# amp_comp.net
KiCad netlist of a schematic drawn in Altium Designer
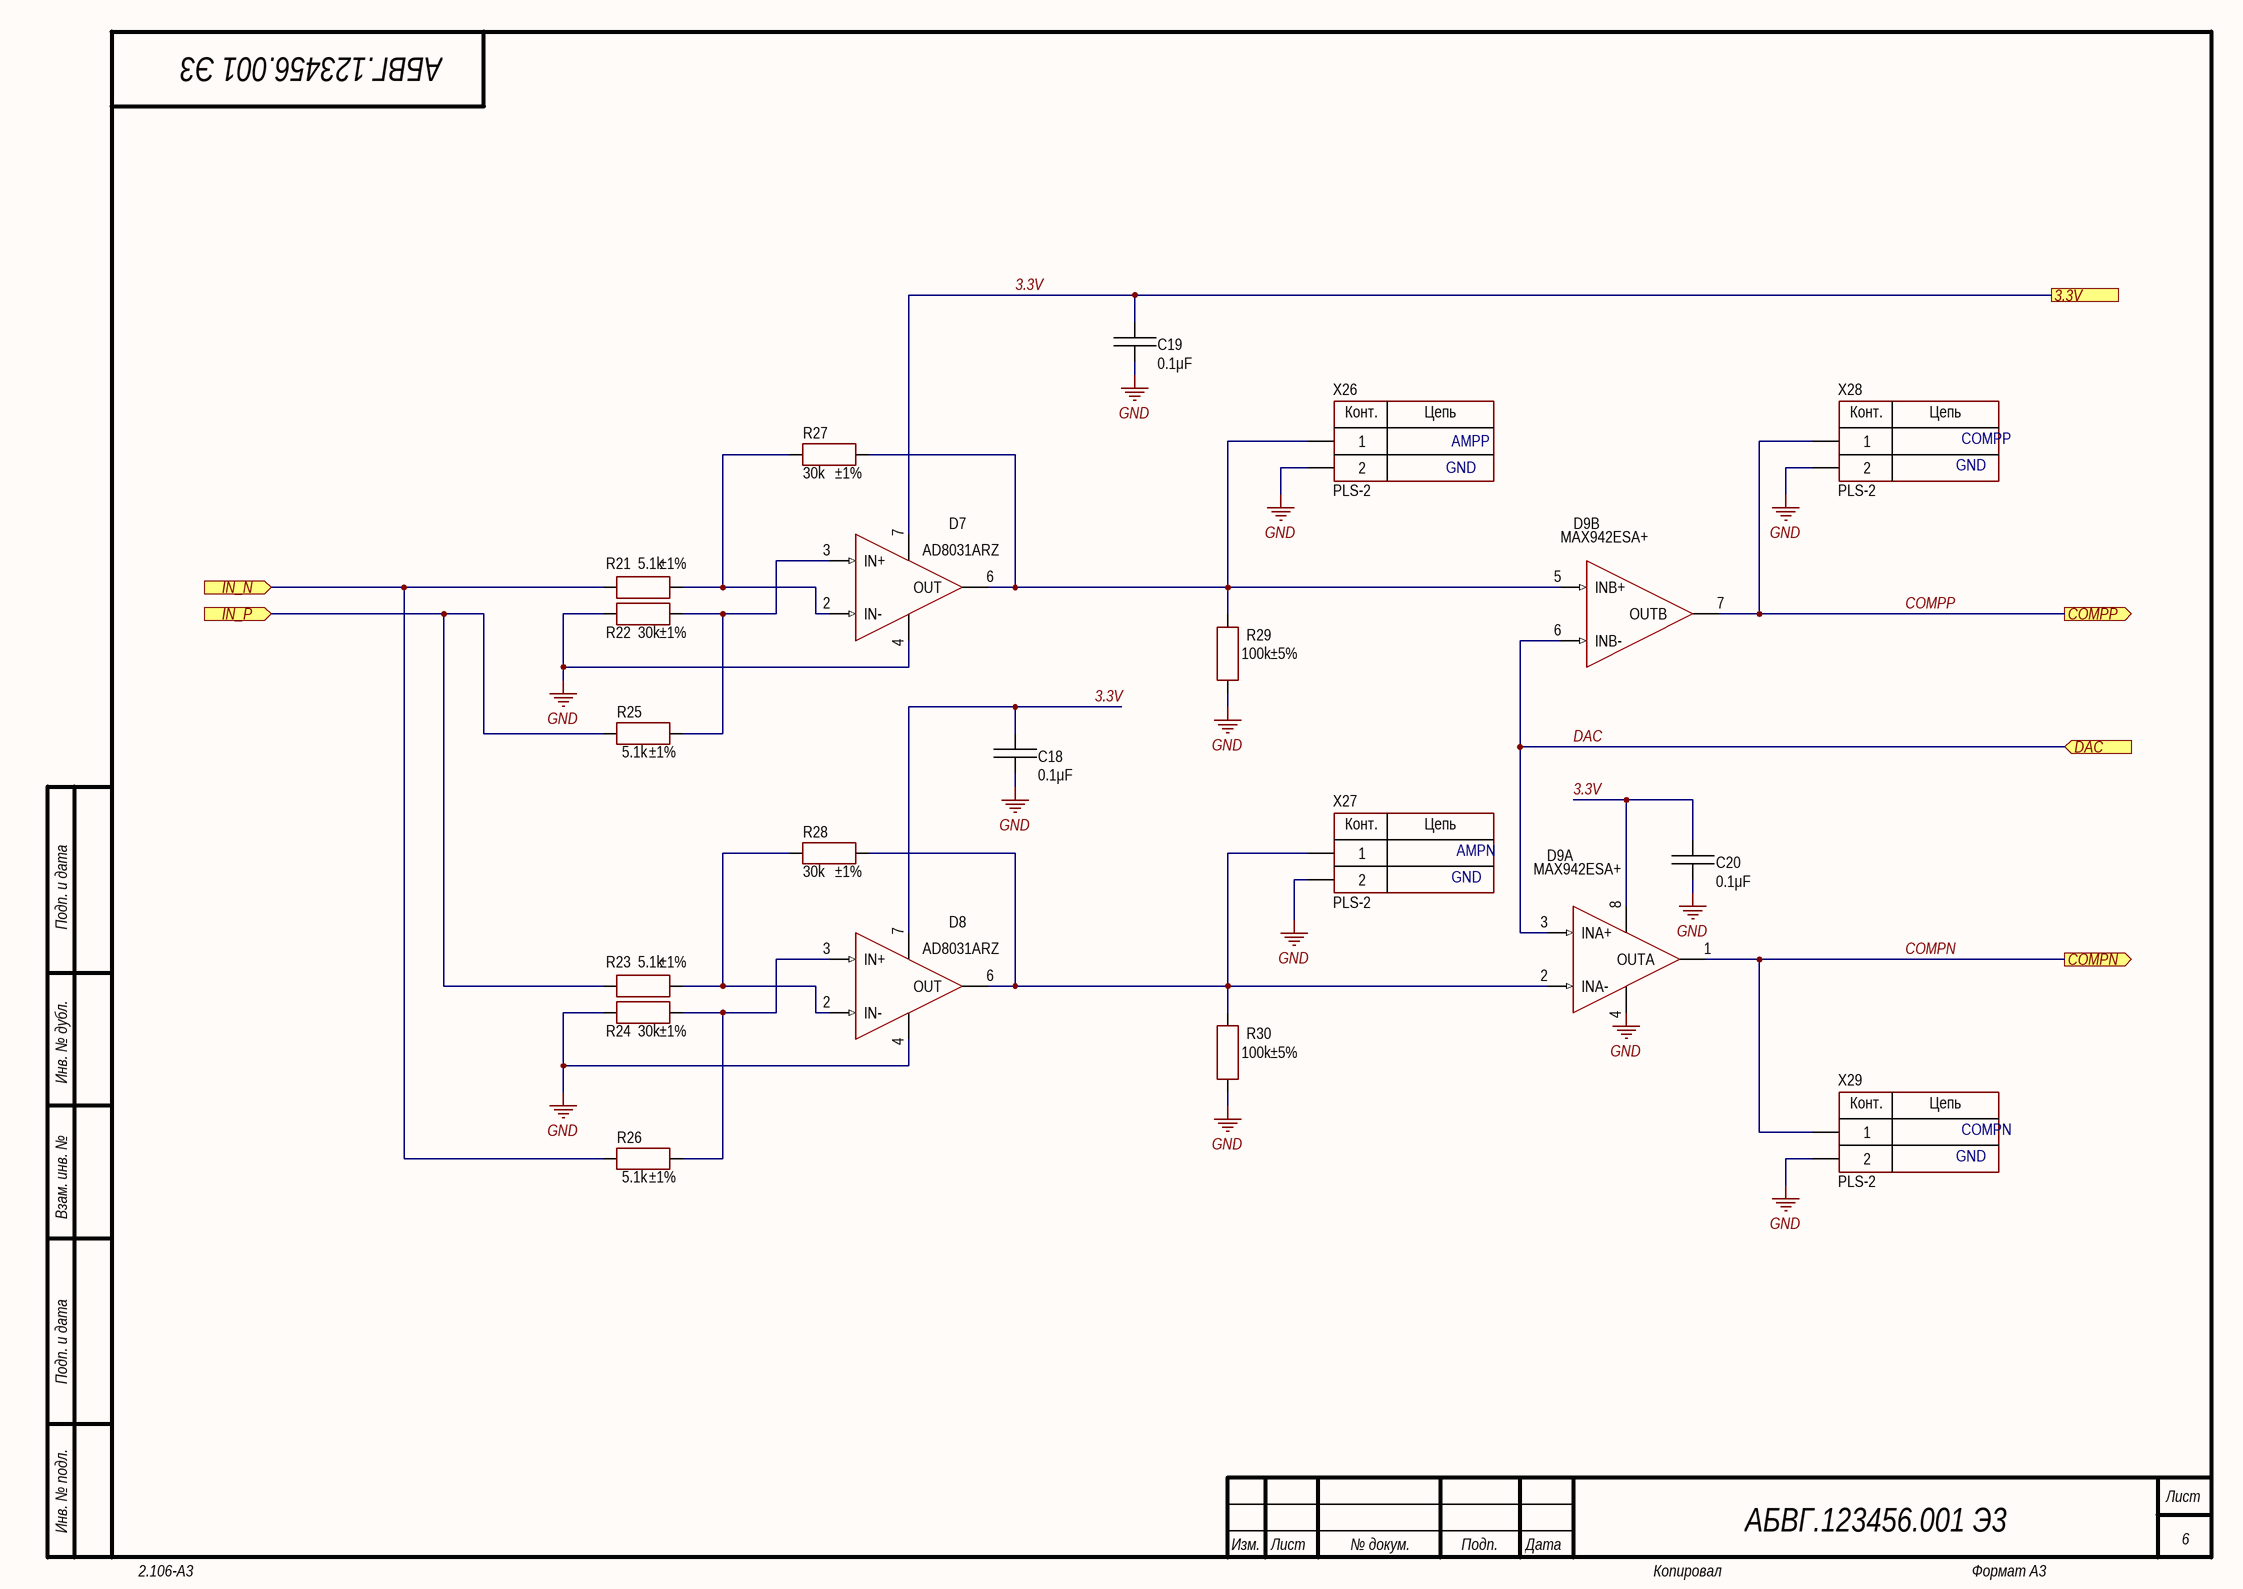
[diagram p0: amp_comp.SchDoc]

(export (version "E")
  (design (tool "Eeschema 10.0.6"))
  (components
    (comp (ref "C18")
      (value "0.1μF")
      (footprint "CAP: 1206")
      (fields
        (field (name "MANUFACTURER") "Murata Electronics")
        (field (name "PARTNUMBER") "GRM319R71H104K")
        (field (name "VALUEMANUFACTURERPARTNUMBER") "Ceramic capacitor, 0.1μF, X7R, ±10%, 50V, 1206, -55...+125°C")
      )
      (libsource (lib "capacitor") (part "Ceramic_1206"))
    )
    (comp (ref "C19")
      (value "0.1μF")
      (footprint "CAP: 1206")
      (fields
        (field (name "MANUFACTURER") "Murata Electronics")
        (field (name "PARTNUMBER") "GRM319R71H104K")
        (field (name "VALUEMANUFACTURERPARTNUMBER") "Ceramic capacitor, 0.1μF, X7R, ±10%, 50V, 1206, -55...+125°C")
      )
      (libsource (lib "capacitor") (part "Ceramic_1206"))
    )
    (comp (ref "C20")
      (value "0.1μF")
      (footprint "CAP: 1206")
      (fields
        (field (name "MANUFACTURER") "Murata Electronics")
        (field (name "PARTNUMBER") "GRM319R71H104K")
        (field (name "VALUEMANUFACTURERPARTNUMBER") "Ceramic capacitor, 0.1μF, X7R, ±10%, 50V, 1206, -55...+125°C")
      )
      (libsource (lib "capacitor") (part "Ceramic_1206"))
    )
    (comp (ref "D7")
      (value "~")
      (footprint "8-SOIC")
      (description "OP amplifier")
      (fields
        (field (name "MANUFACTURER") "Analog Devices Inc.")
        (field (name "VALUEMANUFACTURERPARTNUMBER") "IC op amplifier, Rail-to-Rail, 80MHz, 2.7V ~ 12V, ±1.35V ~ 6V, -40°C ~ 85°C, 8-SOIC")
        (field (name "PARTNUMBER") "AD8031ARZ")
      )
      (libsource (lib "ic-amplifier") (part "AD8031ARZ"))
    )
    (comp (ref "D8")
      (value "~")
      (footprint "8-SOIC")
      (description "OP amplifier")
      (fields
        (field (name "MANUFACTURER") "Analog Devices Inc.")
        (field (name "VALUEMANUFACTURERPARTNUMBER") "IC op amplifier, Rail-to-Rail, 80MHz, 2.7V ~ 12V, ±1.35V ~ 6V, -40°C ~ 85°C, 8-SOIC")
        (field (name "PARTNUMBER") "AD8031ARZ")
      )
      (libsource (lib "ic-amplifier") (part "AD8031ARZ"))
    )
    (comp (ref "D9")
      (value "~")
      (footprint "8-SOIC")
      (description "Comparator")
      (fields
        (field (name "MANUFACTURER") "Maxim Integrated Products")
        (field (name "VALUEMANUFACTURERPARTNUMBER") "IC comparator, Rail-to-Rail, 2.7…6V, -40…85°C, DIP-8(P)/SOIC-8(S)")
        (field (name "PARTNUMBER") "MAX942ESA+")
      )
      (libsource (lib "ic-comparator") (part "MAX942ExA+"))
    )
    (comp (ref "R21")
      (value "5.1k")
      (footprint "RES: 1206")
      (fields
        (field (name "MANUFACTURER") "Yageo")
        (field (name "PARTNUMBER") "RC1206JR-07100RL")
        (field (name "VALUEMANUFACTURERPARTNUMBER") "Resistor film, 5.1k, ±1%, 1206, 0.25W, -55...+125°C")
        (field (name "TOLERANCE") "±1%")
      )
      (libsource (lib "resistor") (part "Resistor_1206"))
    )
    (comp (ref "R22")
      (value "30k")
      (footprint "RES: 1206")
      (fields
        (field (name "MANUFACTURER") "Yageo")
        (field (name "PARTNUMBER") "RC1206JR-07100RL")
        (field (name "VALUEMANUFACTURERPARTNUMBER") "Resistor film, 30k, ±1%, 1206, 0.25W, -55...+125°C")
        (field (name "TOLERANCE") "±1%")
      )
      (libsource (lib "resistor") (part "Resistor_1206"))
    )
    (comp (ref "R23")
      (value "5.1k")
      (footprint "RES: 1206")
      (fields
        (field (name "MANUFACTURER") "Yageo")
        (field (name "PARTNUMBER") "RC1206JR-07100RL")
        (field (name "VALUEMANUFACTURERPARTNUMBER") "Resistor film, 5.1k, ±1%, 1206, 0.25W, -55...+125°C")
        (field (name "TOLERANCE") "±1%")
      )
      (libsource (lib "resistor") (part "Resistor_1206"))
    )
    (comp (ref "R24")
      (value "30k")
      (footprint "RES: 1206")
      (fields
        (field (name "MANUFACTURER") "Yageo")
        (field (name "PARTNUMBER") "RC1206JR-07100RL")
        (field (name "VALUEMANUFACTURERPARTNUMBER") "Resistor film, 30k, ±1%, 1206, 0.25W, -55...+125°C")
        (field (name "TOLERANCE") "±1%")
      )
      (libsource (lib "resistor") (part "Resistor_1206"))
    )
    (comp (ref "R25")
      (value "5.1k")
      (footprint "RES: 1206")
      (fields
        (field (name "MANUFACTURER") "Yageo")
        (field (name "PARTNUMBER") "RC1206JR-07100RL")
        (field (name "VALUEMANUFACTURERPARTNUMBER") "Resistor film, 5.1k, ±1%, 1206, 0.25W, -55...+125°C")
        (field (name "TOLERANCE") "±1%")
      )
      (libsource (lib "resistor") (part "Resistor_1206"))
    )
    (comp (ref "R26")
      (value "5.1k")
      (footprint "RES: 1206")
      (fields
        (field (name "MANUFACTURER") "Yageo")
        (field (name "PARTNUMBER") "RC1206JR-07100RL")
        (field (name "VALUEMANUFACTURERPARTNUMBER") "Resistor film, 5.1k, ±1%, 1206, 0.25W, -55...+125°C")
        (field (name "TOLERANCE") "±1%")
      )
      (libsource (lib "resistor") (part "Resistor_1206"))
    )
    (comp (ref "R27")
      (value "30k")
      (footprint "RES: 1206")
      (fields
        (field (name "MANUFACTURER") "Yageo")
        (field (name "PARTNUMBER") "RC1206JR-07100RL")
        (field (name "VALUEMANUFACTURERPARTNUMBER") "Resistor film, 30k, ±1%, 1206, 0.25W, -55...+125°C")
        (field (name "TOLERANCE") "±1%")
      )
      (libsource (lib "resistor") (part "Resistor_1206"))
    )
    (comp (ref "R28")
      (value "30k")
      (footprint "RES: 1206")
      (fields
        (field (name "MANUFACTURER") "Yageo")
        (field (name "PARTNUMBER") "RC1206JR-07100RL")
        (field (name "VALUEMANUFACTURERPARTNUMBER") "Resistor film, 30k, ±1%, 1206, 0.25W, -55...+125°C")
        (field (name "TOLERANCE") "±1%")
      )
      (libsource (lib "resistor") (part "Resistor_1206"))
    )
    (comp (ref "R29")
      (value "100k")
      (footprint "RES: 1206")
      (fields
        (field (name "MANUFACTURER") "Yageo")
        (field (name "PARTNUMBER") "RC1206JR-07100RL")
        (field (name "VALUEMANUFACTURERPARTNUMBER") "Resistor film, 100k, ±5%, 1206, 0.25W, -55...+125°C")
        (field (name "TOLERANCE") "±5%")
      )
      (libsource (lib "") (part "Resistor_1206_1"))
    )
    (comp (ref "R30")
      (value "100k")
      (footprint "RES: 1206")
      (fields
        (field (name "MANUFACTURER") "Yageo")
        (field (name "PARTNUMBER") "RC1206JR-07100RL")
        (field (name "VALUEMANUFACTURERPARTNUMBER") "Resistor film, 100k, ±5%, 1206, 0.25W, -55...+125°C")
        (field (name "TOLERANCE") "±5%")
      )
      (libsource (lib "") (part "Resistor_1206_1"))
    )
    (comp (ref "X26")
      (value "~")
      (footprint "CON: PLS-2")
      (fields
        (field (name "MANUFACTURER") "Connfly")
        (field (name "VALUEMANUFACTURERPARTNUMBER") "Connector, 2pin, 2.54mm, 500VAC, 3A")
        (field (name "PARTNUMBER") "PLS-2")
        (field (name "COMMENTTEXT") "PLS-2")
      )
      (libsource (lib "connector") (part "PLS-2"))
    )
    (comp (ref "X27")
      (value "~")
      (footprint "CON: PLS-2")
      (fields
        (field (name "MANUFACTURER") "Connfly")
        (field (name "VALUEMANUFACTURERPARTNUMBER") "Connector, 2pin, 2.54mm, 500VAC, 3A")
        (field (name "PARTNUMBER") "PLS-2")
        (field (name "COMMENTTEXT") "PLS-2")
      )
      (libsource (lib "connector") (part "PLS-2"))
    )
    (comp (ref "X28")
      (value "~")
      (footprint "CON: PLS-2")
      (fields
        (field (name "MANUFACTURER") "Connfly")
        (field (name "VALUEMANUFACTURERPARTNUMBER") "Connector, 2pin, 2.54mm, 500VAC, 3A")
        (field (name "PARTNUMBER") "PLS-2")
        (field (name "COMMENTTEXT") "PLS-2")
      )
      (libsource (lib "connector") (part "PLS-2"))
    )
    (comp (ref "X29")
      (value "~")
      (footprint "CON: PLS-2")
      (fields
        (field (name "MANUFACTURER") "Connfly")
        (field (name "VALUEMANUFACTURERPARTNUMBER") "Connector, 2pin, 2.54mm, 500VAC, 3A")
        (field (name "PARTNUMBER") "PLS-2")
        (field (name "COMMENTTEXT") "PLS-2")
      )
      (libsource (lib "connector") (part "PLS-2"))
    )
  )
  (nets
    (net (code "1") (name "/3.3V") (class "Default")
      (node (ref "C18") (pin "2") (pinfunction "2_2") (pintype "passive"))
      (node (ref "C19") (pin "2") (pinfunction "2_2") (pintype "passive"))
      (node (ref "C20") (pin "2") (pinfunction "2_2") (pintype "passive"))
      (node (ref "D7") (pin "7") (pinfunction "V+_7") (pintype "power_in"))
      (node (ref "D8") (pin "7") (pinfunction "V+_7") (pintype "power_in"))
      (node (ref "D9") (pin "8") (pinfunction "V+_8") (pintype "power_in"))
    )
    (net (code "2") (name "/COMPN") (class "Default")
      (node (ref "D9") (pin "1") (pinfunction "OUTA_1") (pintype "passive"))
      (node (ref "X29") (pin "1") (pinfunction "1_1") (pintype "passive"))
    )
    (net (code "3") (name "/COMPP") (class "Default")
      (node (ref "D9") (pin "7") (pinfunction "OUTB_7") (pintype "passive"))
      (node (ref "X28") (pin "1") (pinfunction "1_1") (pintype "passive"))
    )
    (net (code "4") (name "/DAC") (class "Default")
      (node (ref "D9") (pin "3") (pinfunction "INA+_3") (pintype "input"))
      (node (ref "D9") (pin "6") (pinfunction "INB-_6") (pintype "input"))
    )
    (net (code "5") (name "/IN_N") (class "Default")
      (node (ref "R21") (pin "2") (pinfunction "2_2") (pintype "passive"))
      (node (ref "R26") (pin "2") (pinfunction "2_2") (pintype "passive"))
    )
    (net (code "6") (name "/IN_P") (class "Default")
      (node (ref "R23") (pin "2") (pinfunction "2_2") (pintype "passive"))
      (node (ref "R25") (pin "2") (pinfunction "2_2") (pintype "passive"))
    )
    (net (code "7") (name "GND") (class "Default")
      (node (ref "C18") (pin "1") (pinfunction "1_1") (pintype "passive"))
      (node (ref "C19") (pin "1") (pinfunction "1_1") (pintype "passive"))
      (node (ref "C20") (pin "1") (pinfunction "1_1") (pintype "passive"))
      (node (ref "D7") (pin "4") (pinfunction "V-_4") (pintype "power_in"))
      (node (ref "D8") (pin "4") (pinfunction "V-_4") (pintype "power_in"))
      (node (ref "D9") (pin "4") (pinfunction "GND_4") (pintype "power_in"))
      (node (ref "R22") (pin "2") (pinfunction "2_2") (pintype "passive"))
      (node (ref "R24") (pin "2") (pinfunction "2_2") (pintype "passive"))
      (node (ref "R29") (pin "1") (pinfunction "1_1") (pintype "passive"))
      (node (ref "R30") (pin "1") (pinfunction "1_1") (pintype "passive"))
      (node (ref "X26") (pin "2") (pinfunction "2_2") (pintype "passive"))
      (node (ref "X27") (pin "2") (pinfunction "2_2") (pintype "passive"))
      (node (ref "X28") (pin "2") (pinfunction "2_2") (pintype "passive"))
      (node (ref "X29") (pin "2") (pinfunction "2_2") (pintype "passive"))
    )
    (net (code "8") (name "Net-(D7-IN+)") (class "Default")
      (node (ref "D7") (pin "3") (pinfunction "IN+_3") (pintype "input"))
      (node (ref "R22") (pin "1") (pinfunction "1_1") (pintype "passive"))
      (node (ref "R25") (pin "1") (pinfunction "1_1") (pintype "passive"))
    )
    (net (code "9") (name "Net-(D7-IN-)") (class "Default")
      (node (ref "D7") (pin "2") (pinfunction "IN-_2") (pintype "input"))
      (node (ref "R21") (pin "1") (pinfunction "1_1") (pintype "passive"))
      (node (ref "R27") (pin "2") (pinfunction "2_2") (pintype "passive"))
    )
    (net (code "10") (name "Net-(D7-OUT)") (class "Default")
      (node (ref "D7") (pin "6") (pinfunction "OUT_6") (pintype "power_in"))
      (node (ref "D9") (pin "5") (pinfunction "INB+_5") (pintype "input"))
      (node (ref "R27") (pin "1") (pinfunction "1_1") (pintype "passive"))
      (node (ref "R29") (pin "2") (pinfunction "2_2") (pintype "passive"))
      (node (ref "X26") (pin "1") (pinfunction "1_1") (pintype "passive"))
    )
    (net (code "11") (name "Net-(D8-IN+)") (class "Default")
      (node (ref "D8") (pin "3") (pinfunction "IN+_3") (pintype "input"))
      (node (ref "R24") (pin "1") (pinfunction "1_1") (pintype "passive"))
      (node (ref "R26") (pin "1") (pinfunction "1_1") (pintype "passive"))
    )
    (net (code "12") (name "Net-(D8-IN-)") (class "Default")
      (node (ref "D8") (pin "2") (pinfunction "IN-_2") (pintype "input"))
      (node (ref "R23") (pin "1") (pinfunction "1_1") (pintype "passive"))
      (node (ref "R28") (pin "2") (pinfunction "2_2") (pintype "passive"))
    )
    (net (code "13") (name "Net-(D8-OUT)") (class "Default")
      (node (ref "D8") (pin "6") (pinfunction "OUT_6") (pintype "power_in"))
      (node (ref "D9") (pin "2") (pinfunction "INA-_2") (pintype "input"))
      (node (ref "R28") (pin "1") (pinfunction "1_1") (pintype "passive"))
      (node (ref "R30") (pin "2") (pinfunction "2_2") (pintype "passive"))
      (node (ref "X27") (pin "1") (pinfunction "1_1") (pintype "passive"))
    )
  )
)
